# power_supply_design.net
KiCad netlist of a schematic drawn in EAGLE
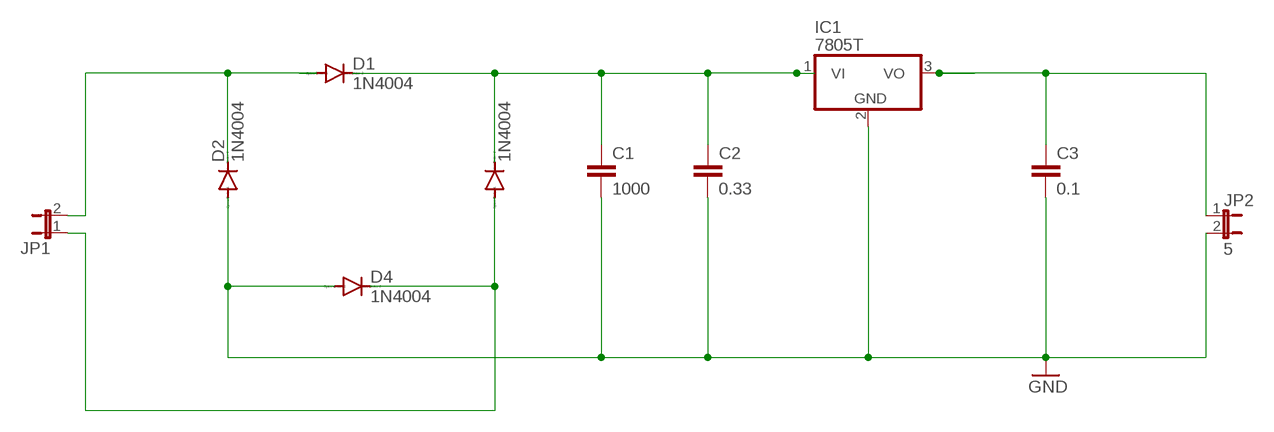
[diagram p0: schematic, sheet 1]

(export (version "E")
  (design (tool "Eeschema 10.0.6"))
  (components
    (comp (ref "C1")
      (value "1000")
      (footprint "eagle-import:C2.5-3")
      (libsource (lib "eagle-import") (part "C2,5-3"))
    )
    (comp (ref "C2")
      (value "0.33")
      (footprint "eagle-import:C2.5-3")
      (libsource (lib "eagle-import") (part "C2,5-3"))
    )
    (comp (ref "C3")
      (value "0.1")
      (footprint "eagle-import:C2.5-3")
      (libsource (lib "eagle-import") (part "C2,5-3"))
    )
    (comp (ref "D1")
      (value "1N4004")
      (footprint "eagle-import:DO41-10")
      (libsource (lib "eagle-import") (part "1N4004"))
    )
    (comp (ref "D2")
      (value "1N4004")
      (footprint "eagle-import:DO41-10")
      (libsource (lib "eagle-import") (part "1N4004"))
    )
    (comp (ref "D3")
      (value "1N4004")
      (footprint "eagle-import:DO41-10")
      (libsource (lib "eagle-import") (part "1N4004"))
    )
    (comp (ref "D4")
      (value "1N4004")
      (footprint "eagle-import:DO41-10")
      (libsource (lib "eagle-import") (part "1N4004"))
    )
    (comp (ref "IC1")
      (value "7805T")
      (footprint "eagle-import:TO220H")
      (libsource (lib "eagle-import") (part "78T05"))
    )
    (comp (ref "JP1")
      (value "12")
      (footprint "eagle-import:JP1")
      (libsource (lib "eagle-import") (part "JP1E"))
    )
    (comp (ref "JP2")
      (value "5")
      (footprint "eagle-import:JP1")
      (libsource (lib "eagle-import") (part "JP1E"))
    )
  )
  (nets
    (net (code "1") (name "GND") (class "Default")
      (node (ref "C1") (pin "2") (pinfunction "2_2") (pintype "passive"))
      (node (ref "C2") (pin "2") (pinfunction "2_2") (pintype "passive"))
      (node (ref "C3") (pin "2") (pinfunction "2_2") (pintype "passive"))
      (node (ref "D2") (pin "A") (pinfunction "A_A") (pintype "passive"))
      (node (ref "D4") (pin "A") (pinfunction "A_A") (pintype "passive"))
      (node (ref "IC1") (pin "2") (pinfunction "GND_2") (pintype "passive"))
      (node (ref "JP2") (pin "2") (pinfunction "2_2") (pintype "passive"))
    )
    (net (code "2") (name "Net-(D1-PadA)") (class "Default")
      (node (ref "D1") (pin "A") (pinfunction "A_A") (pintype "passive"))
      (node (ref "D2") (pin "C") (pinfunction "C_C") (pintype "passive"))
      (node (ref "JP1") (pin "2") (pinfunction "2_2") (pintype "passive"))
    )
    (net (code "3") (name "Net-(D3-PadA)") (class "Default")
      (node (ref "D3") (pin "A") (pinfunction "A_A") (pintype "passive"))
      (node (ref "D4") (pin "C") (pinfunction "C_C") (pintype "passive"))
      (node (ref "JP1") (pin "1") (pinfunction "1_1") (pintype "passive"))
    )
    (net (code "4") (name "Net-(IC1-VI)") (class "Default")
      (node (ref "C1") (pin "1") (pinfunction "1_1") (pintype "passive"))
      (node (ref "C2") (pin "1") (pinfunction "1_1") (pintype "passive"))
      (node (ref "D1") (pin "C") (pinfunction "C_C") (pintype "passive"))
      (node (ref "D3") (pin "C") (pinfunction "C_C") (pintype "passive"))
      (node (ref "IC1") (pin "1") (pinfunction "VI_1") (pintype "input"))
    )
    (net (code "5") (name "Net-(IC1-VO)") (class "Default")
      (node (ref "C3") (pin "1") (pinfunction "1_1") (pintype "passive"))
      (node (ref "IC1") (pin "3") (pinfunction "VO_3") (pintype "passive"))
      (node (ref "JP2") (pin "1") (pinfunction "1_1") (pintype "passive"))
    )
  )
)
